# Connectors.net
KiCad netlist of a schematic drawn in Altium Designer
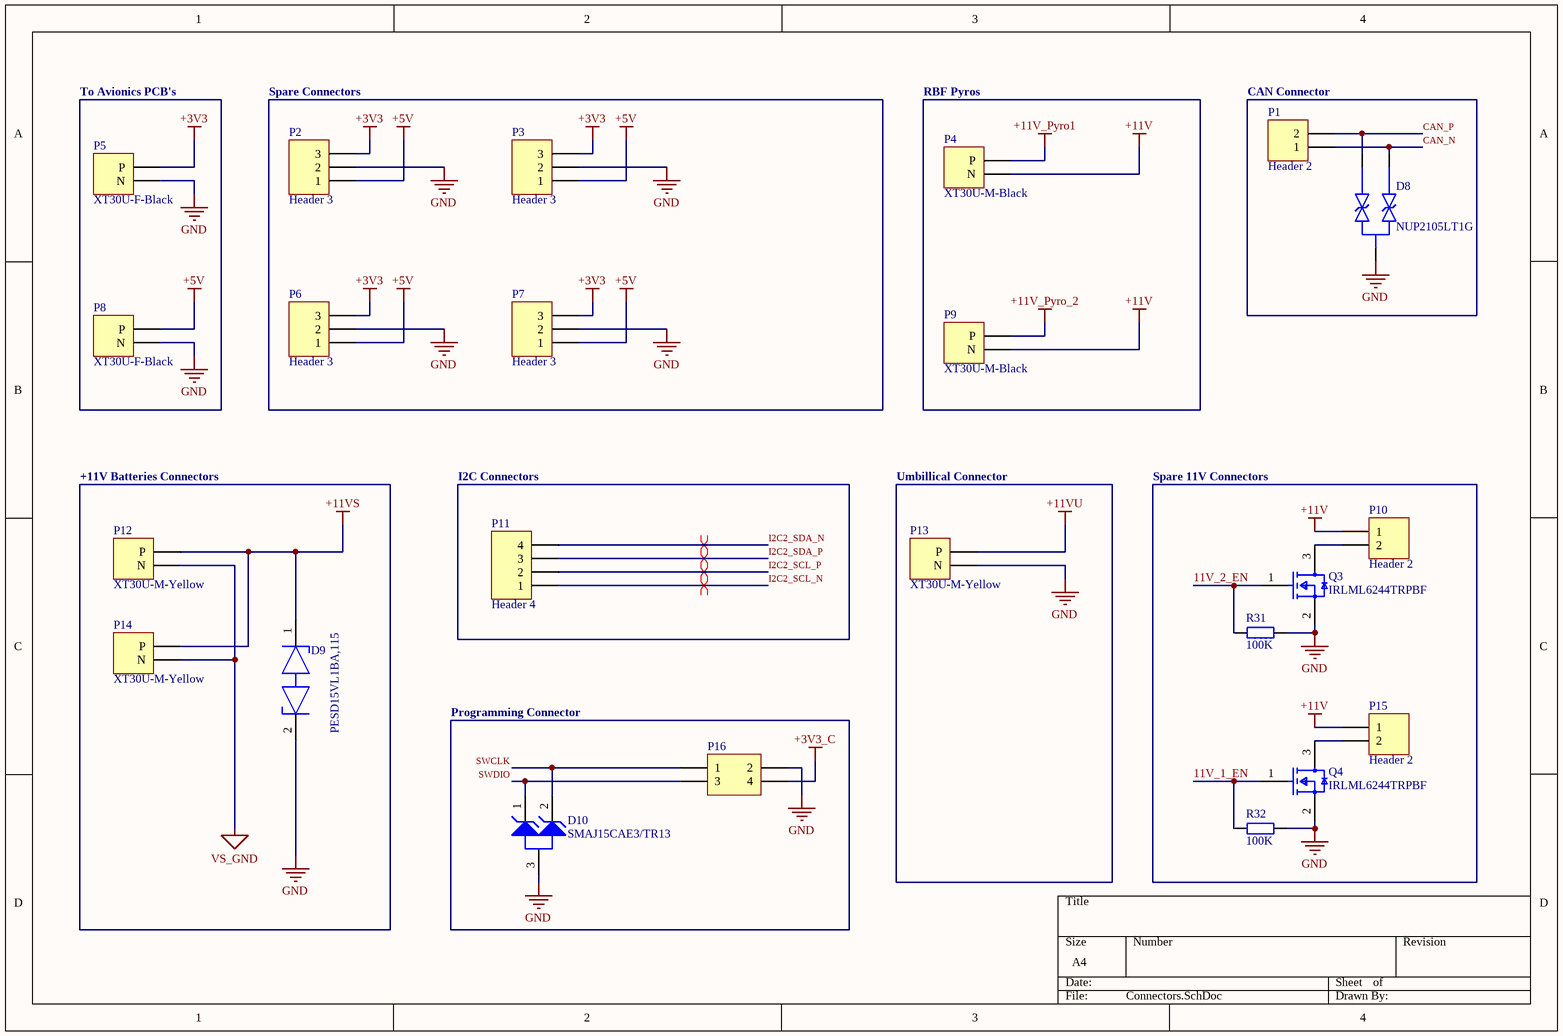
[diagram p0: Connectors.SchDoc]

(export (version "E")
  (design (tool "Eeschema 10.0.6"))
  (components
    (comp (ref "D8")
      (value "NUP2105LT1G")
      (footprint "NUP2105LT1G-Footprint-1")
      (description "Supresor de ESD / diodos TVS 27V CAN BUS Protection")
      (fields (field (name "MANUFACTURER") "Onsemi"))
      (libsource (lib "LEEM UPM") (part "NUP2105LT1G-Symbol-1"))
    )
    (comp (ref "D9")
      (value "PESD15VL1BA,115")
      (footprint "FP-SOD323-CA-IPC_C")
      (description "TVS DIODE 15VWM 44VC SOD323")
      (fields (field (name "MANUFACTURER") "Nexperia"))
      (libsource (lib "Altium Content Vault") (part "99ab701eeba961a21bd2ed46e30d9f3"))
    )
    (comp (ref "D10")
      (value "SMAJ15CAE3/TR13")
      (footprint "ONSC-SOT-723-3-631AA-01_V")
      (description "Supresores de ESD / diodos TVS TVS 400W, Stand-off voltage = 15V, +/- 5%, Bi-dir")
      (fields (field (name "MANUFACTURER") "Micochip Technology"))
      (libsource (lib "LEEM UPM") (part "ONSC-K1K2A3-3"))
    )
    (comp (ref "P1")
      (value "Header 2")
      (footprint "JST XH 2")
      (description "Header, 2-Pin")
      (fields (field (name "ASID PART NUMBER") "Header 2-AS"))
      (libsource (lib "") (part "Header 2_1"))
    )
    (comp (ref "P2")
      (value "Header 3")
      (footprint "JST XH 3")
      (description "Header, 3-Pin")
      (fields (field (name "ASID PART NUMBER") "Header 3-AS"))
      (libsource (lib "LEEM UPM") (part "Header 3"))
    )
    (comp (ref "P3")
      (value "Header 3")
      (footprint "JST XH 3")
      (description "Header, 3-Pin")
      (fields (field (name "ASID PART NUMBER") "Header 3-AS"))
      (libsource (lib "LEEM UPM") (part "Header 3"))
    )
    (comp (ref "P4")
      (value "XT30U-M-Black")
      (footprint "XT30-Footprint-2")
      (description "XT30PW-M公头 Socket,DCsupply,XT30,male,PIN:2")
      (fields (field (name "MANUFACTURER") "AMASS"))
      (libsource (lib "LEEM UPM") (part "XT30PW"))
    )
    (comp (ref "P5")
      (value "XT30U-F-Black")
      (footprint "XT30-Footprint-1")
      (description "XT30PW-M公头 Socket,DCsupply,XT30,male,PIN:2")
      (fields
        (field (name "MANUFACTURER") "AMASS")
        (field (name "MANUFACTURER PART NUMBER") "XT30U-F-Yellow")
      )
      (libsource (lib "LEEM UPM") (part "XT30PW"))
    )
    (comp (ref "P6")
      (value "Header 3")
      (footprint "JST XH 3")
      (description "Header, 3-Pin")
      (fields (field (name "ASID PART NUMBER") "Header 3-AS"))
      (libsource (lib "LEEM UPM") (part "Header 3"))
    )
    (comp (ref "P7")
      (value "Header 3")
      (footprint "JST XH 3")
      (description "Header, 3-Pin")
      (fields (field (name "ASID PART NUMBER") "Header 3-AS"))
      (libsource (lib "LEEM UPM") (part "Header 3"))
    )
    (comp (ref "P8")
      (value "XT30U-F-Black")
      (footprint "XT30-F Negro")
      (description "XT30PW-M公头 Socket,DCsupply,XT30,male,PIN:2")
      (fields (field (name "MANUFACTURER") "AMASS"))
      (libsource (lib "LEEM UPM") (part "XT30PW"))
    )
    (comp (ref "P9")
      (value "XT30U-M-Black")
      (footprint "XT30-Footprint-2")
      (description "XT30PW-M公头 Socket,DCsupply,XT30,male,PIN:2")
      (fields (field (name "MANUFACTURER") "AMASS"))
      (libsource (lib "LEEM UPM") (part "XT30PW"))
    )
    (comp (ref "P10")
      (value "Header 2")
      (footprint "JST XH 2")
      (description "Header, 2-Pin")
      (fields (field (name "ASID PART NUMBER") "Header 2-AS"))
      (libsource (lib "LEEM UPM") (part "Header 2"))
    )
    (comp (ref "P11")
      (value "Header 4")
      (footprint "JST XH")
      (description "Header, 4-Pin")
      (fields (field (name "ASID PART NUMBER") "Header 4-AS"))
      (libsource (lib "LEEM UPM") (part "Header 4"))
    )
    (comp (ref "P12")
      (value "XT30U-M-Yellow")
      (footprint "XT30-Footprint-2")
      (description "XT30PW-M公头 Socket,DCsupply,XT30,male,PIN:2")
      (fields (field (name "MANUFACTURER") "AMASS"))
      (libsource (lib "LEEM UPM") (part "XT30PW"))
    )
    (comp (ref "P13")
      (value "XT30U-M-Yellow")
      (footprint "XT30-Footprint-2")
      (description "XT30PW-M公头 Socket,DCsupply,XT30,male,PIN:2")
      (fields (field (name "MANUFACTURER") "AMASS"))
      (libsource (lib "LEEM UPM") (part "XT30PW"))
    )
    (comp (ref "P14")
      (value "XT30U-M-Yellow")
      (footprint "XT30-Footprint-2")
      (description "XT30PW-M公头 Socket,DCsupply,XT30,male,PIN:2")
      (fields (field (name "MANUFACTURER") "AMASS"))
      (libsource (lib "LEEM UPM") (part "XT30PW"))
    )
    (comp (ref "P15")
      (value "Header 2")
      (footprint "JST XH 2")
      (description "Header, 2-Pin")
      (fields (field (name "ASID PART NUMBER") "Header 2-AS"))
      (libsource (lib "LEEM UPM") (part "Header 2"))
    )
    (comp (ref "P16")
      (value "2 Row 2.54mm Pin Header")
      (footprint "My_2X02")
      (description "Header, 2-Pin, Dual row")
      (libsource (lib "LEEM UPM") (part "Header 2X2"))
    )
    (comp (ref "Q3")
      (value "IRLML6244TRPBF")
      (footprint "FP-Micro3-IPC_C")
      (libsource (lib "LEEM UPM") (part "3b9c635fedb024a5347a57b145af9cc"))
    )
    (comp (ref "Q4")
      (value "IRLML6244TRPBF")
      (footprint "FP-Micro3-IPC_C")
      (libsource (lib "LEEM UPM") (part "3b9c635fedb024a5347a57b145af9cc"))
    )
    (comp (ref "R31")
      (value "100K")
      (footprint "R0603-0.45")
      (description "Resistor, 100K, 0603, 0.1W")
      (fields (field (name "MANUFACTURER") "Wurth") (field (name "MANUFACTURER PART NUMBER") "560112116004"))
      (libsource (lib "IFS_Altium") (part "R"))
    )
    (comp (ref "R32")
      (value "100K")
      (footprint "R0603-0.45")
      (description "Resistor, 100K, 0603, 0.1W")
      (fields (field (name "MANUFACTURER") "Wurth") (field (name "MANUFACTURER PART NUMBER") "560112116004"))
      (libsource (lib "IFS_Altium") (part "R"))
    )
  )
  (nets
    (net (code "1") (name "+3V3") (class "Default")
      (node (ref "P2") (pin "3") (pinfunction "3_3") (pintype "passive"))
      (node (ref "P3") (pin "3") (pinfunction "3_3") (pintype "passive"))
      (node (ref "P5") (pin "P") (pinfunction "P_P") (pintype "passive"))
      (node (ref "P6") (pin "3") (pinfunction "3_3") (pintype "passive"))
      (node (ref "P7") (pin "3") (pinfunction "3_3") (pintype "passive"))
    )
    (net (code "2") (name "+3V3_C") (class "Default")
      (node (ref "P16") (pin "4") (pinfunction "4_4") (pintype "passive"))
    )
    (net (code "3") (name "+5V") (class "Default")
      (node (ref "P2") (pin "1") (pinfunction "1_1") (pintype "passive"))
      (node (ref "P3") (pin "1") (pinfunction "1_1") (pintype "passive"))
      (node (ref "P6") (pin "1") (pinfunction "1_1") (pintype "passive"))
      (node (ref "P7") (pin "1") (pinfunction "1_1") (pintype "passive"))
      (node (ref "P8") (pin "P") (pinfunction "P_P") (pintype "passive"))
    )
    (net (code "4") (name "+11V") (class "Default")
      (node (ref "P10") (pin "1") (pinfunction "1_1") (pintype "passive"))
      (node (ref "P15") (pin "1") (pinfunction "1_1") (pintype "passive"))
      (node (ref "P4") (pin "N") (pinfunction "N_N") (pintype "passive"))
      (node (ref "P9") (pin "N") (pinfunction "N_N") (pintype "passive"))
    )
    (net (code "5") (name "+11VS") (class "Default")
      (node (ref "D9") (pin "1") (pinfunction "1_1") (pintype "passive"))
      (node (ref "P12") (pin "P") (pinfunction "P_P") (pintype "passive"))
      (node (ref "P14") (pin "P") (pinfunction "P_P") (pintype "passive"))
    )
    (net (code "6") (name "+11VU") (class "Default")
      (node (ref "P13") (pin "P") (pinfunction "P_P") (pintype "passive"))
    )
    (net (code "7") (name "+11V_Pyro1") (class "Default")
      (node (ref "P4") (pin "P") (pinfunction "P_P") (pintype "passive"))
    )
    (net (code "8") (name "+11V_Pyro_2") (class "Default")
      (node (ref "P9") (pin "P") (pinfunction "P_P") (pintype "passive"))
    )
    (net (code "9") (name "/11V_1_EN") (class "Default")
      (node (ref "Q4") (pin "1") (pinfunction "G_1") (pintype "passive"))
      (node (ref "R32") (pin "1") (pinfunction "1_1") (pintype "passive"))
    )
    (net (code "10") (name "/11V_2_EN") (class "Default")
      (node (ref "Q3") (pin "1") (pinfunction "G_1") (pintype "passive"))
      (node (ref "R31") (pin "1") (pinfunction "1_1") (pintype "passive"))
    )
    (net (code "11") (name "/CAN_N") (class "Default")
      (node (ref "D8") (pin "1") (pinfunction "1_1") (pintype "passive"))
      (node (ref "P1") (pin "1") (pinfunction "1_1") (pintype "passive"))
    )
    (net (code "12") (name "/CAN_P") (class "Default")
      (node (ref "D8") (pin "2") (pinfunction "2_2") (pintype "passive"))
      (node (ref "P1") (pin "2") (pinfunction "2_2") (pintype "passive"))
    )
    (net (code "13") (name "/I2C2_SCL_N") (class "Default")
      (node (ref "P11") (pin "1") (pinfunction "1_1") (pintype "passive"))
    )
    (net (code "14") (name "/I2C2_SCL_P") (class "Default")
      (node (ref "P11") (pin "2") (pinfunction "2_2") (pintype "passive"))
    )
    (net (code "15") (name "/I2C2_SDA_N") (class "Default")
      (node (ref "P11") (pin "4") (pinfunction "4_4") (pintype "passive"))
    )
    (net (code "16") (name "/I2C2_SDA_P") (class "Default")
      (node (ref "P11") (pin "3") (pinfunction "3_3") (pintype "passive"))
    )
    (net (code "17") (name "/SWCLK") (class "Default")
      (node (ref "D10") (pin "2") (pinfunction "K2_2") (pintype "passive"))
      (node (ref "P16") (pin "1") (pinfunction "1_1") (pintype "passive"))
    )
    (net (code "18") (name "/SWDIO") (class "Default")
      (node (ref "D10") (pin "1") (pinfunction "K1_1") (pintype "passive"))
      (node (ref "P16") (pin "3") (pinfunction "3_3") (pintype "passive"))
    )
    (net (code "19") (name "GND") (class "Default")
      (node (ref "D10") (pin "3") (pinfunction "A_3") (pintype "passive"))
      (node (ref "D8") (pin "3") (pinfunction "3_3") (pintype "passive"))
      (node (ref "D9") (pin "2") (pinfunction "2_2") (pintype "passive"))
      (node (ref "P13") (pin "N") (pinfunction "N_N") (pintype "passive"))
      (node (ref "P16") (pin "2") (pinfunction "2_2") (pintype "passive"))
      (node (ref "P2") (pin "2") (pinfunction "2_2") (pintype "passive"))
      (node (ref "P3") (pin "2") (pinfunction "2_2") (pintype "passive"))
      (node (ref "P5") (pin "N") (pinfunction "N_N") (pintype "passive"))
      (node (ref "P6") (pin "2") (pinfunction "2_2") (pintype "passive"))
      (node (ref "P7") (pin "2") (pinfunction "2_2") (pintype "passive"))
      (node (ref "P8") (pin "N") (pinfunction "N_N") (pintype "passive"))
      (node (ref "Q3") (pin "2") (pinfunction "S_2") (pintype "passive"))
      (node (ref "Q4") (pin "2") (pinfunction "S_2") (pintype "passive"))
      (node (ref "R31") (pin "2") (pinfunction "2_2") (pintype "passive"))
      (node (ref "R32") (pin "2") (pinfunction "2_2") (pintype "passive"))
    )
    (net (code "20") (name "Net-(Q3-D)") (class "Default")
      (node (ref "P10") (pin "2") (pinfunction "2_2") (pintype "passive"))
      (node (ref "Q3") (pin "3") (pinfunction "D_3") (pintype "passive"))
    )
    (net (code "21") (name "Net-(Q4-D)") (class "Default")
      (node (ref "P15") (pin "2") (pinfunction "2_2") (pintype "passive"))
      (node (ref "Q4") (pin "3") (pinfunction "D_3") (pintype "passive"))
    )
    (net (code "22") (name "VS_GND") (class "Default")
      (node (ref "P12") (pin "N") (pinfunction "N_N") (pintype "passive"))
      (node (ref "P14") (pin "N") (pinfunction "N_N") (pintype "passive"))
    )
  )
)
